# LEDboard.net
KiCad netlist of a schematic drawn in EAGLE
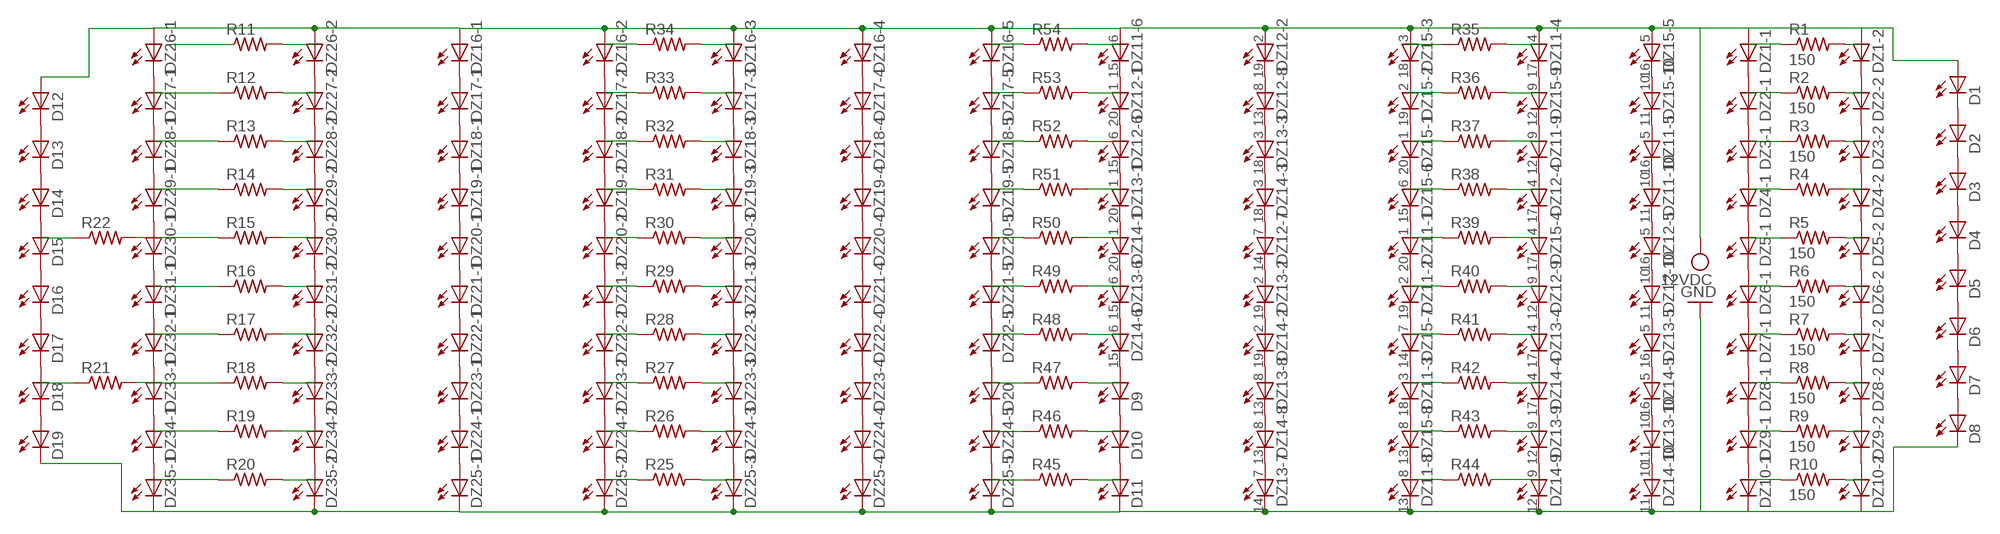
[diagram p0: schematic, sheet 1]

(export (version "E")
  (design (tool "Eeschema 10.0.6"))
  (components
    (comp (ref "D1")
      (value "U57X32")
      (footprint "eagle-import:U57X32")
      (libsource (lib "eagle-import") (part "U57X32"))
    )
    (comp (ref "D2")
      (value "U57X32")
      (footprint "eagle-import:U57X32")
      (libsource (lib "eagle-import") (part "U57X32"))
    )
    (comp (ref "D3")
      (value "U57X32")
      (footprint "eagle-import:U57X32")
      (libsource (lib "eagle-import") (part "U57X32"))
    )
    (comp (ref "D4")
      (value "U57X32")
      (footprint "eagle-import:U57X32")
      (libsource (lib "eagle-import") (part "U57X32"))
    )
    (comp (ref "D5")
      (value "U57X32")
      (footprint "eagle-import:U57X32")
      (libsource (lib "eagle-import") (part "U57X32"))
    )
    (comp (ref "D6")
      (value "U57X32")
      (footprint "eagle-import:U57X32")
      (libsource (lib "eagle-import") (part "U57X32"))
    )
    (comp (ref "D7")
      (value "U57X32")
      (footprint "eagle-import:U57X32")
      (libsource (lib "eagle-import") (part "U57X32"))
    )
    (comp (ref "D8")
      (value "U57X32")
      (footprint "eagle-import:U57X32")
      (libsource (lib "eagle-import") (part "U57X32"))
    )
    (comp (ref "D9")
      (value "U57X32")
      (footprint "eagle-import:U57X32")
      (libsource (lib "eagle-import") (part "U57X32"))
    )
    (comp (ref "D10")
      (value "U57X32")
      (footprint "eagle-import:U57X32")
      (libsource (lib "eagle-import") (part "U57X32"))
    )
    (comp (ref "D11")
      (value "U57X32")
      (footprint "eagle-import:U57X32")
      (libsource (lib "eagle-import") (part "U57X32"))
    )
    (comp (ref "D12")
      (value "U57X32")
      (footprint "eagle-import:U57X32")
      (libsource (lib "eagle-import") (part "U57X32"))
    )
    (comp (ref "D13")
      (value "U57X32")
      (footprint "eagle-import:U57X32")
      (libsource (lib "eagle-import") (part "U57X32"))
    )
    (comp (ref "D14")
      (value "U57X32")
      (footprint "eagle-import:U57X32")
      (libsource (lib "eagle-import") (part "U57X32"))
    )
    (comp (ref "D15")
      (value "U57X32")
      (footprint "eagle-import:U57X32")
      (libsource (lib "eagle-import") (part "U57X32"))
    )
    (comp (ref "D16")
      (value "U57X32")
      (footprint "eagle-import:U57X32")
      (libsource (lib "eagle-import") (part "U57X32"))
    )
    (comp (ref "D17")
      (value "U57X32")
      (footprint "eagle-import:U57X32")
      (libsource (lib "eagle-import") (part "U57X32"))
    )
    (comp (ref "D18")
      (value "U57X32")
      (footprint "eagle-import:U57X32")
      (libsource (lib "eagle-import") (part "U57X32"))
    )
    (comp (ref "D19")
      (value "U57X32")
      (footprint "eagle-import:U57X32")
      (libsource (lib "eagle-import") (part "U57X32"))
    )
    (comp (ref "D20")
      (value "U57X32")
      (footprint "eagle-import:U57X32")
      (libsource (lib "eagle-import") (part "U57X32"))
    )
    (comp (ref "DZ1")
      (value "LZR182")
      (footprint "eagle-import:LZR182")
      (libsource (lib "eagle-import") (part "LZR182"))
    )
    (comp (ref "DZ2")
      (value "LZR182")
      (footprint "eagle-import:LZR182")
      (libsource (lib "eagle-import") (part "LZR182"))
    )
    (comp (ref "DZ3")
      (value "LZR182")
      (footprint "eagle-import:LZR182")
      (libsource (lib "eagle-import") (part "LZR182"))
    )
    (comp (ref "DZ4")
      (value "LZR182")
      (footprint "eagle-import:LZR182")
      (libsource (lib "eagle-import") (part "LZR182"))
    )
    (comp (ref "DZ5")
      (value "LZR182")
      (footprint "eagle-import:LZR182")
      (libsource (lib "eagle-import") (part "LZR182"))
    )
    (comp (ref "DZ6")
      (value "LZR182")
      (footprint "eagle-import:LZR182")
      (libsource (lib "eagle-import") (part "LZR182"))
    )
    (comp (ref "DZ7")
      (value "LZR182")
      (footprint "eagle-import:LZR182")
      (libsource (lib "eagle-import") (part "LZR182"))
    )
    (comp (ref "DZ8")
      (value "LZR182")
      (footprint "eagle-import:LZR182")
      (libsource (lib "eagle-import") (part "LZR182"))
    )
    (comp (ref "DZ9")
      (value "LZR182")
      (footprint "eagle-import:LZR182")
      (libsource (lib "eagle-import") (part "LZR182"))
    )
    (comp (ref "DZ10")
      (value "LZR182")
      (footprint "eagle-import:LZR182")
      (libsource (lib "eagle-import") (part "LZR182"))
    )
    (comp (ref "DZ11")
      (value "LB10")
      (footprint "eagle-import:LB10")
      (libsource (lib "eagle-import") (part "LB10"))
    )
    (comp (ref "DZ12")
      (value "LB10")
      (footprint "eagle-import:LB10")
      (libsource (lib "eagle-import") (part "LB10"))
    )
    (comp (ref "DZ13")
      (value "LB10")
      (footprint "eagle-import:LB10")
      (libsource (lib "eagle-import") (part "LB10"))
    )
    (comp (ref "DZ14")
      (value "LB10")
      (footprint "eagle-import:LB10")
      (libsource (lib "eagle-import") (part "LB10"))
    )
    (comp (ref "DZ15")
      (value "LB10")
      (footprint "eagle-import:LB10")
      (libsource (lib "eagle-import") (part "LB10"))
    )
    (comp (ref "DZ16")
      (value "LZR185")
      (footprint "eagle-import:LZR185")
      (libsource (lib "eagle-import") (part "LZR185"))
    )
    (comp (ref "DZ17")
      (value "LZR185")
      (footprint "eagle-import:LZR185")
      (libsource (lib "eagle-import") (part "LZR185"))
    )
    (comp (ref "DZ18")
      (value "LZR185")
      (footprint "eagle-import:LZR185")
      (libsource (lib "eagle-import") (part "LZR185"))
    )
    (comp (ref "DZ19")
      (value "LZR185")
      (footprint "eagle-import:LZR185")
      (libsource (lib "eagle-import") (part "LZR185"))
    )
    (comp (ref "DZ20")
      (value "LZR185")
      (footprint "eagle-import:LZR185")
      (libsource (lib "eagle-import") (part "LZR185"))
    )
    (comp (ref "DZ21")
      (value "LZR185")
      (footprint "eagle-import:LZR185")
      (libsource (lib "eagle-import") (part "LZR185"))
    )
    (comp (ref "DZ22")
      (value "LZR185")
      (footprint "eagle-import:LZR185")
      (libsource (lib "eagle-import") (part "LZR185"))
    )
    (comp (ref "DZ23")
      (value "LZR185")
      (footprint "eagle-import:LZR185")
      (libsource (lib "eagle-import") (part "LZR185"))
    )
    (comp (ref "DZ24")
      (value "LZR185")
      (footprint "eagle-import:LZR185")
      (libsource (lib "eagle-import") (part "LZR185"))
    )
    (comp (ref "DZ25")
      (value "LZR185")
      (footprint "eagle-import:LZR185")
      (libsource (lib "eagle-import") (part "LZR185"))
    )
    (comp (ref "DZ26")
      (value "LZR182")
      (footprint "eagle-import:LZR182")
      (libsource (lib "eagle-import") (part "LZR182"))
    )
    (comp (ref "DZ27")
      (value "LZR182")
      (footprint "eagle-import:LZR182")
      (libsource (lib "eagle-import") (part "LZR182"))
    )
    (comp (ref "DZ28")
      (value "LZR182")
      (footprint "eagle-import:LZR182")
      (libsource (lib "eagle-import") (part "LZR182"))
    )
    (comp (ref "DZ29")
      (value "LZR182")
      (footprint "eagle-import:LZR182")
      (libsource (lib "eagle-import") (part "LZR182"))
    )
    (comp (ref "DZ30")
      (value "LZR182")
      (footprint "eagle-import:LZR182")
      (libsource (lib "eagle-import") (part "LZR182"))
    )
    (comp (ref "DZ31")
      (value "LZR182")
      (footprint "eagle-import:LZR182")
      (libsource (lib "eagle-import") (part "LZR182"))
    )
    (comp (ref "DZ32")
      (value "LZR182")
      (footprint "eagle-import:LZR182")
      (libsource (lib "eagle-import") (part "LZR182"))
    )
    (comp (ref "DZ33")
      (value "LZR182")
      (footprint "eagle-import:LZR182")
      (libsource (lib "eagle-import") (part "LZR182"))
    )
    (comp (ref "DZ34")
      (value "LZR182")
      (footprint "eagle-import:LZR182")
      (libsource (lib "eagle-import") (part "LZR182"))
    )
    (comp (ref "DZ35")
      (value "LZR182")
      (footprint "eagle-import:LZR182")
      (libsource (lib "eagle-import") (part "LZR182"))
    )
    (comp (ref "R1")
      (value "150")
      (footprint "eagle-import:0204V")
      (libsource (lib "eagle-import") (part "R-US_0204/2V"))
    )
    (comp (ref "R2")
      (value "150")
      (footprint "eagle-import:0204V")
      (libsource (lib "eagle-import") (part "R-US_0204/2V"))
    )
    (comp (ref "R3")
      (value "150")
      (footprint "eagle-import:0204V")
      (libsource (lib "eagle-import") (part "R-US_0204/2V"))
    )
    (comp (ref "R4")
      (value "R-US_0204/2V")
      (footprint "eagle-import:0204V")
      (libsource (lib "eagle-import") (part "R-US_0204/2V"))
    )
    (comp (ref "R5")
      (value "150")
      (footprint "eagle-import:0204V")
      (libsource (lib "eagle-import") (part "R-US_0204/2V"))
    )
    (comp (ref "R6")
      (value "150")
      (footprint "eagle-import:0204V")
      (libsource (lib "eagle-import") (part "R-US_0204/2V"))
    )
    (comp (ref "R7")
      (value "150")
      (footprint "eagle-import:0204V")
      (libsource (lib "eagle-import") (part "R-US_0204/2V"))
    )
    (comp (ref "R8")
      (value "150")
      (footprint "eagle-import:0204V")
      (libsource (lib "eagle-import") (part "R-US_0204/2V"))
    )
    (comp (ref "R9")
      (value "150")
      (footprint "eagle-import:0204V")
      (libsource (lib "eagle-import") (part "R-US_0204/2V"))
    )
    (comp (ref "R10")
      (value "150")
      (footprint "eagle-import:0204V")
      (libsource (lib "eagle-import") (part "R-US_0204/2V"))
    )
    (comp (ref "R11")
      (value "R-US_0204/2V")
      (footprint "eagle-import:0204V")
      (libsource (lib "eagle-import") (part "R-US_0204/2V"))
    )
    (comp (ref "R12")
      (value "R-US_0204/2V")
      (footprint "eagle-import:0204V")
      (libsource (lib "eagle-import") (part "R-US_0204/2V"))
    )
    (comp (ref "R13")
      (value "R-US_0204/2V")
      (footprint "eagle-import:0204V")
      (libsource (lib "eagle-import") (part "R-US_0204/2V"))
    )
    (comp (ref "R14")
      (value "R-US_0204/2V")
      (footprint "eagle-import:0204V")
      (libsource (lib "eagle-import") (part "R-US_0204/2V"))
    )
    (comp (ref "R15")
      (value "R-US_0204/2V")
      (footprint "eagle-import:0204V")
      (libsource (lib "eagle-import") (part "R-US_0204/2V"))
    )
    (comp (ref "R16")
      (value "R-US_0204/2V")
      (footprint "eagle-import:0204V")
      (libsource (lib "eagle-import") (part "R-US_0204/2V"))
    )
    (comp (ref "R17")
      (value "R-US_0204/2V")
      (footprint "eagle-import:0204V")
      (libsource (lib "eagle-import") (part "R-US_0204/2V"))
    )
    (comp (ref "R18")
      (value "R-US_0204/2V")
      (footprint "eagle-import:0204V")
      (libsource (lib "eagle-import") (part "R-US_0204/2V"))
    )
    (comp (ref "R19")
      (value "R-US_0204/2V")
      (footprint "eagle-import:0204V")
      (libsource (lib "eagle-import") (part "R-US_0204/2V"))
    )
    (comp (ref "R20")
      (value "R-US_0204/2V")
      (footprint "eagle-import:0204V")
      (libsource (lib "eagle-import") (part "R-US_0204/2V"))
    )
    (comp (ref "R21")
      (value "R-US_0204/2V")
      (footprint "eagle-import:0204V")
      (libsource (lib "eagle-import") (part "R-US_0204/2V"))
    )
    (comp (ref "R22")
      (value "R-US_0204/2V")
      (footprint "eagle-import:0204V")
      (libsource (lib "eagle-import") (part "R-US_0204/2V"))
    )
    (comp (ref "R25")
      (value "R-US_0204/2V")
      (footprint "eagle-import:0204V")
      (libsource (lib "eagle-import") (part "R-US_0204/2V"))
    )
    (comp (ref "R26")
      (value "R-US_0204/2V")
      (footprint "eagle-import:0204V")
      (libsource (lib "eagle-import") (part "R-US_0204/2V"))
    )
    (comp (ref "R27")
      (value "R-US_0204/2V")
      (footprint "eagle-import:0204V")
      (libsource (lib "eagle-import") (part "R-US_0204/2V"))
    )
    (comp (ref "R28")
      (value "R-US_0204/2V")
      (footprint "eagle-import:0204V")
      (libsource (lib "eagle-import") (part "R-US_0204/2V"))
    )
    (comp (ref "R29")
      (value "R-US_0204/2V")
      (footprint "eagle-import:0204V")
      (libsource (lib "eagle-import") (part "R-US_0204/2V"))
    )
    (comp (ref "R30")
      (value "R-US_0204/2V")
      (footprint "eagle-import:0204V")
      (libsource (lib "eagle-import") (part "R-US_0204/2V"))
    )
    (comp (ref "R31")
      (value "R-US_0204/2V")
      (footprint "eagle-import:0204V")
      (libsource (lib "eagle-import") (part "R-US_0204/2V"))
    )
    (comp (ref "R32")
      (value "R-US_0204/2V")
      (footprint "eagle-import:0204V")
      (libsource (lib "eagle-import") (part "R-US_0204/2V"))
    )
    (comp (ref "R33")
      (value "R-US_0204/2V")
      (footprint "eagle-import:0204V")
      (libsource (lib "eagle-import") (part "R-US_0204/2V"))
    )
    (comp (ref "R34")
      (value "R-US_0204/2V")
      (footprint "eagle-import:0204V")
      (libsource (lib "eagle-import") (part "R-US_0204/2V"))
    )
    (comp (ref "R35")
      (value "R-US_0204/2V")
      (footprint "eagle-import:0204V")
      (libsource (lib "eagle-import") (part "R-US_0204/2V"))
    )
    (comp (ref "R36")
      (value "R-US_0204/2V")
      (footprint "eagle-import:0204V")
      (libsource (lib "eagle-import") (part "R-US_0204/2V"))
    )
    (comp (ref "R37")
      (value "R-US_0204/2V")
      (footprint "eagle-import:0204V")
      (libsource (lib "eagle-import") (part "R-US_0204/2V"))
    )
    (comp (ref "R38")
      (value "R-US_0204/2V")
      (footprint "eagle-import:0204V")
      (libsource (lib "eagle-import") (part "R-US_0204/2V"))
    )
    (comp (ref "R39")
      (value "R-US_0204/2V")
      (footprint "eagle-import:0204V")
      (libsource (lib "eagle-import") (part "R-US_0204/2V"))
    )
    (comp (ref "R40")
      (value "R-US_0204/2V")
      (footprint "eagle-import:0204V")
      (libsource (lib "eagle-import") (part "R-US_0204/2V"))
    )
    (comp (ref "R41")
      (value "R-US_0204/2V")
      (footprint "eagle-import:0204V")
      (libsource (lib "eagle-import") (part "R-US_0204/2V"))
    )
    (comp (ref "R42")
      (value "R-US_0204/2V")
      (footprint "eagle-import:0204V")
      (libsource (lib "eagle-import") (part "R-US_0204/2V"))
    )
    (comp (ref "R43")
      (value "R-US_0204/2V")
      (footprint "eagle-import:0204V")
      (libsource (lib "eagle-import") (part "R-US_0204/2V"))
    )
    (comp (ref "R44")
      (value "R-US_0204/2V")
      (footprint "eagle-import:0204V")
      (libsource (lib "eagle-import") (part "R-US_0204/2V"))
    )
    (comp (ref "R45")
      (value "R-US_0204/2V")
      (footprint "eagle-import:0204V")
      (libsource (lib "eagle-import") (part "R-US_0204/2V"))
    )
    (comp (ref "R46")
      (value "R-US_0204/2V")
      (footprint "eagle-import:0204V")
      (libsource (lib "eagle-import") (part "R-US_0204/2V"))
    )
    (comp (ref "R47")
      (value "R-US_0204/2V")
      (footprint "eagle-import:0204V")
      (libsource (lib "eagle-import") (part "R-US_0204/2V"))
    )
    (comp (ref "R48")
      (value "R-US_0204/2V")
      (footprint "eagle-import:0204V")
      (libsource (lib "eagle-import") (part "R-US_0204/2V"))
    )
    (comp (ref "R49")
      (value "R-US_0204/2V")
      (footprint "eagle-import:0204V")
      (libsource (lib "eagle-import") (part "R-US_0204/2V"))
    )
    (comp (ref "R50")
      (value "R-US_0204/2V")
      (footprint "eagle-import:0204V")
      (libsource (lib "eagle-import") (part "R-US_0204/2V"))
    )
    (comp (ref "R51")
      (value "R-US_0204/2V")
      (footprint "eagle-import:0204V")
      (libsource (lib "eagle-import") (part "R-US_0204/2V"))
    )
    (comp (ref "R52")
      (value "R-US_0204/2V")
      (footprint "eagle-import:0204V")
      (libsource (lib "eagle-import") (part "R-US_0204/2V"))
    )
    (comp (ref "R53")
      (value "R-US_0204/2V")
      (footprint "eagle-import:0204V")
      (libsource (lib "eagle-import") (part "R-US_0204/2V"))
    )
    (comp (ref "R54")
      (value "R-US_0204/2V")
      (footprint "eagle-import:0204V")
      (libsource (lib "eagle-import") (part "R-US_0204/2V"))
    )
  )
  (nets
    (net (code "1") (name "12VDC") (class "Default")
      (node (ref "D1") (pin "A") (pinfunction "A_A") (pintype "passive"))
      (node (ref "D12") (pin "A") (pinfunction "A_A") (pintype "passive"))
      (node (ref "DZ1") (pin "A1") (pinfunction "A_A1") (pintype "passive"))
      (node (ref "DZ1") (pin "A2") (pinfunction "A_A2") (pintype "passive"))
      (node (ref "DZ11") (pin "4") (pinfunction "A_4") (pintype "passive"))
      (node (ref "DZ11") (pin "6") (pinfunction "A_6") (pintype "passive"))
      (node (ref "DZ12") (pin "2") (pinfunction "A_2") (pintype "passive"))
      (node (ref "DZ15") (pin "3") (pinfunction "A_3") (pintype "passive"))
      (node (ref "DZ15") (pin "5") (pinfunction "A_5") (pintype "passive"))
      (node (ref "DZ16") (pin "A1") (pinfunction "A_A1") (pintype "passive"))
      (node (ref "DZ16") (pin "A2") (pinfunction "A_A2") (pintype "passive"))
      (node (ref "DZ16") (pin "A3") (pinfunction "A_A3") (pintype "passive"))
      (node (ref "DZ16") (pin "A4") (pinfunction "A_A4") (pintype "passive"))
      (node (ref "DZ16") (pin "A5") (pinfunction "A_A5") (pintype "passive"))
      (node (ref "DZ26") (pin "A1") (pinfunction "A_A1") (pintype "passive"))
      (node (ref "DZ26") (pin "A2") (pinfunction "A_A2") (pintype "passive"))
    )
    (net (code "2") (name "GND") (class "Default")
      (node (ref "D11") (pin "K") (pinfunction "C_K") (pintype "passive"))
      (node (ref "D19") (pin "K") (pinfunction "C_K") (pintype "passive"))
      (node (ref "D8") (pin "K") (pinfunction "C_K") (pintype "passive"))
      (node (ref "DZ10") (pin "K1") (pinfunction "C_K1") (pintype "passive"))
      (node (ref "DZ10") (pin "K2") (pinfunction "C_K2") (pintype "passive"))
      (node (ref "DZ11") (pin "13") (pinfunction "C_13") (pintype "passive"))
      (node (ref "DZ13") (pin "14") (pinfunction "C_14") (pintype "passive"))
      (node (ref "DZ14") (pin "11") (pinfunction "C_11") (pintype "passive"))
      (node (ref "DZ14") (pin "12") (pinfunction "C_12") (pintype "passive"))
      (node (ref "DZ25") (pin "K1") (pinfunction "C_K1") (pintype "passive"))
      (node (ref "DZ25") (pin "K2") (pinfunction "C_K2") (pintype "passive"))
      (node (ref "DZ25") (pin "K3") (pinfunction "C_K3") (pintype "passive"))
      (node (ref "DZ25") (pin "K4") (pinfunction "C_K4") (pintype "passive"))
      (node (ref "DZ25") (pin "K5") (pinfunction "C_K5") (pintype "passive"))
      (node (ref "DZ35") (pin "K1") (pinfunction "C_K1") (pintype "passive"))
      (node (ref "DZ35") (pin "K2") (pinfunction "C_K2") (pintype "passive"))
    )
    (net (code "3") (name "Net-(D1-C)") (class "Default")
      (node (ref "D1") (pin "K") (pinfunction "C_K") (pintype "passive"))
      (node (ref "D2") (pin "A") (pinfunction "A_A") (pintype "passive"))
    )
    (net (code "4") (name "Net-(D2-C)") (class "Default")
      (node (ref "D2") (pin "K") (pinfunction "C_K") (pintype "passive"))
      (node (ref "D3") (pin "A") (pinfunction "A_A") (pintype "passive"))
    )
    (net (code "5") (name "Net-(D3-C)") (class "Default")
      (node (ref "D3") (pin "K") (pinfunction "C_K") (pintype "passive"))
      (node (ref "D4") (pin "A") (pinfunction "A_A") (pintype "passive"))
    )
    (net (code "6") (name "Net-(D4-C)") (class "Default")
      (node (ref "D4") (pin "K") (pinfunction "C_K") (pintype "passive"))
      (node (ref "D5") (pin "A") (pinfunction "A_A") (pintype "passive"))
    )
    (net (code "7") (name "Net-(D5-C)") (class "Default")
      (node (ref "D5") (pin "K") (pinfunction "C_K") (pintype "passive"))
      (node (ref "D6") (pin "A") (pinfunction "A_A") (pintype "passive"))
    )
    (net (code "8") (name "Net-(D6-C)") (class "Default")
      (node (ref "D6") (pin "K") (pinfunction "C_K") (pintype "passive"))
      (node (ref "D7") (pin "A") (pinfunction "A_A") (pintype "passive"))
    )
    (net (code "9") (name "Net-(D7-C)") (class "Default")
      (node (ref "D7") (pin "K") (pinfunction "C_K") (pintype "passive"))
      (node (ref "D8") (pin "A") (pinfunction "A_A") (pintype "passive"))
    )
    (net (code "10") (name "Net-(D9-C)") (class "Default")
      (node (ref "D10") (pin "A") (pinfunction "A_A") (pintype "passive"))
      (node (ref "D9") (pin "K") (pinfunction "C_K") (pintype "passive"))
    )
    (net (code "11") (name "Net-(D10-C)") (class "Default")
      (node (ref "D10") (pin "K") (pinfunction "C_K") (pintype "passive"))
      (node (ref "D11") (pin "A") (pinfunction "A_A") (pintype "passive"))
    )
    (net (code "12") (name "Net-(D12-C)") (class "Default")
      (node (ref "D12") (pin "K") (pinfunction "C_K") (pintype "passive"))
      (node (ref "D13") (pin "A") (pinfunction "A_A") (pintype "passive"))
    )
    (net (code "13") (name "Net-(D13-C)") (class "Default")
      (node (ref "D13") (pin "K") (pinfunction "C_K") (pintype "passive"))
      (node (ref "D14") (pin "A") (pinfunction "A_A") (pintype "passive"))
    )
    (net (code "14") (name "Net-(D14-C)") (class "Default")
      (node (ref "D14") (pin "K") (pinfunction "C_K") (pintype "passive"))
      (node (ref "D15") (pin "A") (pinfunction "A_A") (pintype "passive"))
    )
    (net (code "15") (name "Net-(D15-C)") (class "Default")
      (node (ref "D15") (pin "K") (pinfunction "C_K") (pintype "passive"))
      (node (ref "D16") (pin "A") (pinfunction "A_A") (pintype "passive"))
    )
    (net (code "16") (name "Net-(D16-C)") (class "Default")
      (node (ref "D16") (pin "K") (pinfunction "C_K") (pintype "passive"))
      (node (ref "D17") (pin "A") (pinfunction "A_A") (pintype "passive"))
    )
    (net (code "17") (name "Net-(D17-C)") (class "Default")
      (node (ref "D17") (pin "K") (pinfunction "C_K") (pintype "passive"))
      (node (ref "D18") (pin "A") (pinfunction "A_A") (pintype "passive"))
    )
    (net (code "18") (name "Net-(D18-C)") (class "Default")
      (node (ref "D18") (pin "K") (pinfunction "C_K") (pintype "passive"))
      (node (ref "D19") (pin "A") (pinfunction "A_A") (pintype "passive"))
    )
    (net (code "19") (name "Net-(D20-C)") (class "Default")
      (node (ref "D20") (pin "K") (pinfunction "C_K") (pintype "passive"))
      (node (ref "DZ24") (pin "A5") (pinfunction "A_A5") (pintype "passive"))
    )
    (net (code "20") (name "Net-(DZ1A-C)") (class "Default")
      (node (ref "DZ1") (pin "K1") (pinfunction "C_K1") (pintype "passive"))
      (node (ref "DZ2") (pin "A1") (pinfunction "A_A1") (pintype "passive"))
    )
    (net (code "21") (name "Net-(DZ1B-C)") (class "Default")
      (node (ref "DZ1") (pin "K2") (pinfunction "C_K2") (pintype "passive"))
      (node (ref "DZ2") (pin "A2") (pinfunction "A_A2") (pintype "passive"))
    )
    (net (code "22") (name "Net-(DZ2A-C)") (class "Default")
      (node (ref "DZ2") (pin "K1") (pinfunction "C_K1") (pintype "passive"))
      (node (ref "DZ3") (pin "A1") (pinfunction "A_A1") (pintype "passive"))
    )
    (net (code "23") (name "Net-(DZ2B-C)") (class "Default")
      (node (ref "DZ2") (pin "K2") (pinfunction "C_K2") (pintype "passive"))
      (node (ref "DZ3") (pin "A2") (pinfunction "A_A2") (pintype "passive"))
    )
    (net (code "24") (name "Net-(DZ3A-C)") (class "Default")
      (node (ref "DZ3") (pin "K1") (pinfunction "C_K1") (pintype "passive"))
      (node (ref "DZ4") (pin "A1") (pinfunction "A_A1") (pintype "passive"))
    )
    (net (code "25") (name "Net-(DZ3B-C)") (class "Default")
      (node (ref "DZ3") (pin "K2") (pinfunction "C_K2") (pintype "passive"))
      (node (ref "DZ4") (pin "A2") (pinfunction "A_A2") (pintype "passive"))
    )
    (net (code "26") (name "Net-(DZ4A-C)") (class "Default")
      (node (ref "DZ4") (pin "K1") (pinfunction "C_K1") (pintype "passive"))
      (node (ref "DZ5") (pin "A1") (pinfunction "A_A1") (pintype "passive"))
    )
    (net (code "27") (name "Net-(DZ4B-C)") (class "Default")
      (node (ref "DZ4") (pin "K2") (pinfunction "C_K2") (pintype "passive"))
      (node (ref "DZ5") (pin "A2") (pinfunction "A_A2") (pintype "passive"))
    )
    (net (code "28") (name "Net-(DZ5A-C)") (class "Default")
      (node (ref "DZ5") (pin "K1") (pinfunction "C_K1") (pintype "passive"))
      (node (ref "DZ6") (pin "A1") (pinfunction "A_A1") (pintype "passive"))
    )
    (net (code "29") (name "Net-(DZ5B-C)") (class "Default")
      (node (ref "DZ5") (pin "K2") (pinfunction "C_K2") (pintype "passive"))
      (node (ref "DZ6") (pin "A2") (pinfunction "A_A2") (pintype "passive"))
    )
    (net (code "30") (name "Net-(DZ6A-C)") (class "Default")
      (node (ref "DZ6") (pin "K1") (pinfunction "C_K1") (pintype "passive"))
      (node (ref "DZ7") (pin "A1") (pinfunction "A_A1") (pintype "passive"))
    )
    (net (code "31") (name "Net-(DZ6B-C)") (class "Default")
      (node (ref "DZ6") (pin "K2") (pinfunction "C_K2") (pintype "passive"))
      (node (ref "DZ7") (pin "A2") (pinfunction "A_A2") (pintype "passive"))
    )
    (net (code "32") (name "Net-(DZ7A-C)") (class "Default")
      (node (ref "DZ7") (pin "K1") (pinfunction "C_K1") (pintype "passive"))
      (node (ref "DZ8") (pin "A1") (pinfunction "A_A1") (pintype "passive"))
    )
    (net (code "33") (name "Net-(DZ7B-C)") (class "Default")
      (node (ref "DZ7") (pin "K2") (pinfunction "C_K2") (pintype "passive"))
      (node (ref "DZ8") (pin "A2") (pinfunction "A_A2") (pintype "passive"))
    )
    (net (code "34") (name "Net-(DZ8A-C)") (class "Default")
      (node (ref "DZ8") (pin "K1") (pinfunction "C_K1") (pintype "passive"))
      (node (ref "DZ9") (pin "A1") (pinfunction "A_A1") (pintype "passive"))
    )
    (net (code "35") (name "Net-(DZ8B-C)") (class "Default")
      (node (ref "DZ8") (pin "K2") (pinfunction "C_K2") (pintype "passive"))
      (node (ref "DZ9") (pin "A2") (pinfunction "A_A2") (pintype "passive"))
    )
    (net (code "36") (name "Net-(DZ10A-A)") (class "Default")
      (node (ref "DZ10") (pin "A1") (pinfunction "A_A1") (pintype "passive"))
      (node (ref "DZ9") (pin "K1") (pinfunction "C_K1") (pintype "passive"))
    )
    (net (code "37") (name "Net-(DZ10B-A)") (class "Default")
      (node (ref "DZ10") (pin "A2") (pinfunction "A_A2") (pintype "passive"))
      (node (ref "DZ9") (pin "K2") (pinfunction "C_K2") (pintype "passive"))
    )
    (net (code "38") (name "Net-(DZ11A-A)") (class "Default")
      (node (ref "DZ11") (pin "1") (pinfunction "A_1") (pintype "passive"))
      (node (ref "DZ15") (pin "15") (pinfunction "C_15") (pintype "passive"))
    )
    (net (code "39") (name "Net-(DZ11A-C)") (class "Default")
      (node (ref "DZ11") (pin "2") (pinfunction "A_2") (pintype "passive"))
      (node (ref "DZ11") (pin "20") (pinfunction "C_20") (pintype "passive"))
    )
    (net (code "40") (name "Net-(DZ11B-A)") (class "Default")
      (node (ref "DZ11") (pin "10") (pinfunction "A_10") (pintype "passive"))
      (node (ref "DZ11") (pin "16") (pinfunction "C_16") (pintype "passive"))
    )
    (net (code "41") (name "Net-(DZ11B-C)") (class "Default")
      (node (ref "DZ11") (pin "11") (pinfunction "C_11") (pintype "passive"))
      (node (ref "DZ12") (pin "5") (pinfunction "A_5") (pintype "passive"))
    )
    (net (code "42") (name "Net-(DZ11C-C)") (class "Default")
      (node (ref "DZ11") (pin "19") (pinfunction "C_19") (pintype "passive"))
      (node (ref "DZ15") (pin "7") (pinfunction "A_7") (pintype "passive"))
    )
    (net (code "43") (name "Net-(DZ11D-A)") (class "Default")
      (node (ref "DZ11") (pin "3") (pinfunction "A_3") (pintype "passive"))
      (node (ref "DZ15") (pin "14") (pinfunction "C_14") (pintype "passive"))
    )
    (net (code "44") (name "Net-(DZ11D-C)") (class "Default")
      (node (ref "DZ11") (pin "18") (pinfunction "C_18") (pintype "passive"))
      (node (ref "DZ15") (pin "8") (pinfunction "A_8") (pintype "passive"))
    )
    (net (code "45") (name "Net-(DZ11E-C)") (class "Default")
      (node (ref "DZ11") (pin "17") (pinfunction "C_17") (pintype "passive"))
      (node (ref "DZ15") (pin "9") (pinfunction "A_9") (pintype "passive"))
    )
    (net (code "46") (name "Net-(DZ11F-A)") (class "Default")
      (node (ref "DZ11") (pin "5") (pinfunction "A_5") (pintype "passive"))
      (node (ref "DZ15") (pin "11") (pinfunction "C_11") (pintype "passive"))
    )
    (net (code "47") (name "Net-(DZ11G-C)") (class "Default")
      (node (ref "DZ11") (pin "15") (pinfunction "C_15") (pintype "passive"))
      (node (ref "DZ12") (pin "1") (pinfunction "A_1") (pintype "passive"))
    )
    (net (code "48") (name "Net-(DZ11I-A)") (class "Default")
      (node (ref "DZ11") (pin "8") (pinfunction "A_8") (pintype "passive"))
      (node (ref "DZ15") (pin "13") (pinfunction "C_13") (pintype "passive"))
    )
    (net (code "49") (name "Net-(DZ11J-A)") (class "Default")
      (node (ref "DZ11") (pin "9") (pinfunction "A_9") (pintype "passive"))
      (node (ref "DZ15") (pin "12") (pinfunction "C_12") (pintype "passive"))
    )
    (net (code "50") (name "Net-(DZ11J-C)") (class "Default")
      (node (ref "DZ11") (pin "12") (pinfunction "C_12") (pintype "passive"))
      (node (ref "DZ12") (pin "4") (pinfunction "A_4") (pintype "passive"))
    )
    (net (code "51") (name "Net-(DZ12A-C)") (class "Default")
      (node (ref "DZ12") (pin "20") (pinfunction "C_20") (pintype "passive"))
      (node (ref "DZ12") (pin "6") (pinfunction "A_6") (pintype "passive"))
    )
    (net (code "52") (name "Net-(DZ12B-A)") (class "Default")
      (node (ref "DZ12") (pin "10") (pinfunction "A_10") (pintype "passive"))
      (node (ref "DZ12") (pin "16") (pinfunction "C_16") (pintype "passive"))
    )
    (net (code "53") (name "Net-(DZ12B-C)") (class "Default")
      (node (ref "DZ12") (pin "11") (pinfunction "C_11") (pintype "passive"))
      (node (ref "DZ13") (pin "5") (pinfunction "A_5") (pintype "passive"))
    )
    (net (code "54") (name "Net-(DZ12C-C)") (class "Default")
      (node (ref "DZ12") (pin "19") (pinfunction "C_19") (pintype "passive"))
      (node (ref "DZ12") (pin "8") (pinfunction "A_8") (pintype "passive"))
    )
    (net (code "55") (name "Net-(DZ12E-C)") (class "Default")
      (node (ref "DZ12") (pin "17") (pinfunction "C_17") (pintype "passive"))
      (node (ref "DZ15") (pin "4") (pinfunction "A_4") (pintype "passive"))
    )
    (net (code "56") (name "Net-(DZ12G-C)") (class "Default")
      (node (ref "DZ12") (pin "15") (pinfunction "C_15") (pintype "passive"))
      (node (ref "DZ13") (pin "1") (pinfunction "A_1") (pintype "passive"))
    )
    (net (code "57") (name "Net-(DZ12H-A)") (class "Default")
      (node (ref "DZ12") (pin "7") (pinfunction "A_7") (pintype "passive"))
      (node (ref "DZ14") (pin "18") (pinfunction "C_18") (pintype "passive"))
    )
    (net (code "58") (name "Net-(DZ12H-C)") (class "Default")
      (node (ref "DZ12") (pin "14") (pinfunction "C_14") (pintype "passive"))
      (node (ref "DZ13") (pin "2") (pinfunction "A_2") (pintype "passive"))
    )
    (net (code "59") (name "Net-(DZ12I-C)") (class "Default")
      (node (ref "DZ12") (pin "13") (pinfunction "C_13") (pintype "passive"))
      (node (ref "DZ13") (pin "3") (pinfunction "A_3") (pintype "passive"))
    )
    (net (code "60") (name "Net-(DZ12J-A)") (class "Default")
      (node (ref "DZ12") (pin "9") (pinfunction "A_9") (pintype "passive"))
      (node (ref "DZ15") (pin "17") (pinfunction "C_17") (pintype "passive"))
    )
    (net (code "61") (name "Net-(DZ12J-C)") (class "Default")
      (node (ref "DZ12") (pin "12") (pinfunction "C_12") (pintype "passive"))
      (node (ref "DZ13") (pin "4") (pinfunction "A_4") (pintype "passive"))
    )
    (net (code "62") (name "Net-(DZ13A-C)") (class "Default")
      (node (ref "DZ13") (pin "20") (pinfunction "C_20") (pintype "passive"))
      (node (ref "DZ14") (pin "1") (pinfunction "A_1") (pintype "passive"))
    )
    (net (code "63") (name "Net-(DZ13B-A)") (class "Default")
      (node (ref "DZ13") (pin "10") (pinfunction "A_10") (pintype "passive"))
      (node (ref "DZ14") (pin "16") (pinfunction "C_16") (pintype "passive"))
    )
    (net (code "64") (name "Net-(DZ13B-C)") (class "Default")
      (node (ref "DZ13") (pin "11") (pinfunction "C_11") (pintype "passive"))
      (node (ref "DZ14") (pin "10") (pinfunction "A_10") (pintype "passive"))
    )
    (net (code "65") (name "Net-(DZ13C-C)") (class "Default")
      (node (ref "DZ13") (pin "19") (pinfunction "C_19") (pintype "passive"))
      (node (ref "DZ14") (pin "2") (pinfunction "A_2") (pintype "passive"))
    )
    (net (code "66") (name "Net-(DZ13D-C)") (class "Default")
      (node (ref "DZ13") (pin "18") (pinfunction "C_18") (pintype "passive"))
      (node (ref "DZ14") (pin "3") (pinfunction "A_3") (pintype "passive"))
    )
    (net (code "67") (name "Net-(DZ13E-C)") (class "Default")
      (node (ref "DZ13") (pin "17") (pinfunction "C_17") (pintype "passive"))
      (node (ref "DZ14") (pin "4") (pinfunction "A_4") (pintype "passive"))
    )
    (net (code "68") (name "Net-(DZ13F-C)") (class "Default")
      (node (ref "DZ13") (pin "16") (pinfunction "C_16") (pintype "passive"))
      (node (ref "DZ14") (pin "5") (pinfunction "A_5") (pintype "passive"))
    )
    (net (code "69") (name "Net-(DZ13G-A)") (class "Default")
      (node (ref "DZ13") (pin "6") (pinfunction "A_6") (pintype "passive"))
      (node (ref "DZ14") (pin "20") (pinfunction "C_20") (pintype "passive"))
    )
    (net (code "70") (name "Net-(DZ13G-C)") (class "Default")
      (node (ref "DZ13") (pin "15") (pinfunction "C_15") (pintype "passive"))
      (node (ref "DZ14") (pin "6") (pinfunction "A_6") (pintype "passive"))
    )
    (net (code "71") (name "Net-(DZ13H-A)") (class "Default")
      (node (ref "DZ13") (pin "7") (pinfunction "A_7") (pintype "passive"))
      (node (ref "DZ14") (pin "13") (pinfunction "C_13") (pintype "passive"))
    )
    (net (code "72") (name "Net-(DZ13I-A)") (class "Default")
      (node (ref "DZ13") (pin "8") (pinfunction "A_8") (pintype "passive"))
      (node (ref "DZ14") (pin "19") (pinfunction "C_19") (pintype "passive"))
    )
    (net (code "73") (name "Net-(DZ13I-C)") (class "Default")
      (node (ref "DZ13") (pin "13") (pinfunction "C_13") (pintype "passive"))
      (node (ref "DZ14") (pin "8") (pinfunction "A_8") (pintype "passive"))
    )
    (net (code "74") (name "Net-(DZ13J-A)") (class "Default")
      (node (ref "DZ13") (pin "9") (pinfunction "A_9") (pintype "passive"))
      (node (ref "DZ14") (pin "17") (pinfunction "C_17") (pintype "passive"))
    )
    (net (code "75") (name "Net-(DZ13J-C)") (class "Default")
      (node (ref "DZ13") (pin "12") (pinfunction "C_12") (pintype "passive"))
      (node (ref "DZ14") (pin "9") (pinfunction "A_9") (pintype "passive"))
    )
    (net (code "76") (name "Net-(DZ14G-C)") (class "Default")
      (node (ref "D9") (pin "A") (pinfunction "A_A") (pintype "passive"))
      (node (ref "DZ14") (pin "15") (pinfunction "C_15") (pintype "passive"))
    )
    (net (code "77") (name "Net-(DZ15A-A)") (class "Default")
      (node (ref "DZ15") (pin "1") (pinfunction "A_1") (pintype "passive"))
      (node (ref "DZ15") (pin "19") (pinfunction "C_19") (pintype "passive"))
    )
    (net (code "78") (name "Net-(DZ15A-C)") (class "Default")
      (node (ref "DZ15") (pin "20") (pinfunction "C_20") (pintype "passive"))
      (node (ref "DZ15") (pin "6") (pinfunction "A_6") (pintype "passive"))
    )
    (net (code "79") (name "Net-(DZ15B-A)") (class "Default")
      (node (ref "DZ15") (pin "10") (pinfunction "A_10") (pintype "passive"))
      (node (ref "DZ15") (pin "16") (pinfunction "C_16") (pintype "passive"))
    )
    (net (code "80") (name "Net-(DZ15C-A)") (class "Default")
      (node (ref "DZ15") (pin "18") (pinfunction "C_18") (pintype "passive"))
      (node (ref "DZ15") (pin "2") (pinfunction "A_2") (pintype "passive"))
    )
    (net (code "81") (name "Net-(DZ16A-C)") (class "Default")
      (node (ref "DZ16") (pin "K1") (pinfunction "C_K1") (pintype "passive"))
      (node (ref "DZ17") (pin "A1") (pinfunction "A_A1") (pintype "passive"))
    )
    (net (code "82") (name "Net-(DZ16B-C)") (class "Default")
      (node (ref "DZ16") (pin "K2") (pinfunction "C_K2") (pintype "passive"))
      (node (ref "DZ17") (pin "A2") (pinfunction "A_A2") (pintype "passive"))
    )
    (net (code "83") (name "Net-(DZ16C-C)") (class "Default")
      (node (ref "DZ16") (pin "K3") (pinfunction "C_K3") (pintype "passive"))
      (node (ref "DZ17") (pin "A3") (pinfunction "A_A3") (pintype "passive"))
    )
    (net (code "84") (name "Net-(DZ16D-C)") (class "Default")
      (node (ref "DZ16") (pin "K4") (pinfunction "C_K4") (pintype "passive"))
      (node (ref "DZ17") (pin "A4") (pinfunction "A_A4") (pintype "passive"))
    )
    (net (code "85") (name "Net-(DZ16E-C)") (class "Default")
      (node (ref "DZ16") (pin "K5") (pinfunction "C_K5") (pintype "passive"))
      (node (ref "DZ17") (pin "A5") (pinfunction "A_A5") (pintype "passive"))
    )
    (net (code "86") (name "Net-(DZ17A-C)") (class "Default")
      (node (ref "DZ17") (pin "K1") (pinfunction "C_K1") (pintype "passive"))
      (node (ref "DZ18") (pin "A1") (pinfunction "A_A1") (pintype "passive"))
    )
    (net (code "87") (name "Net-(DZ17B-C)") (class "Default")
      (node (ref "DZ17") (pin "K2") (pinfunction "C_K2") (pintype "passive"))
      (node (ref "DZ18") (pin "A2") (pinfunction "A_A2") (pintype "passive"))
    )
    (net (code "88") (name "Net-(DZ17C-C)") (class "Default")
      (node (ref "DZ17") (pin "K3") (pinfunction "C_K3") (pintype "passive"))
      (node (ref "DZ18") (pin "A3") (pinfunction "A_A3") (pintype "passive"))
    )
    (net (code "89") (name "Net-(DZ17D-C)") (class "Default")
      (node (ref "DZ17") (pin "K4") (pinfunction "C_K4") (pintype "passive"))
      (node (ref "DZ18") (pin "A4") (pinfunction "A_A4") (pintype "passive"))
    )
    (net (code "90") (name "Net-(DZ17E-C)") (class "Default")
      (node (ref "DZ17") (pin "K5") (pinfunction "C_K5") (pintype "passive"))
      (node (ref "DZ18") (pin "A5") (pinfunction "A_A5") (pintype "passive"))
    )
    (net (code "91") (name "Net-(DZ18A-C)") (class "Default")
      (node (ref "DZ18") (pin "K1") (pinfunction "C_K1") (pintype "passive"))
      (node (ref "DZ19") (pin "A1") (pinfunction "A_A1") (pintype "passive"))
    )
    (net (code "92") (name "Net-(DZ18B-C)") (class "Default")
      (node (ref "DZ18") (pin "K2") (pinfunction "C_K2") (pintype "passive"))
      (node (ref "DZ19") (pin "A2") (pinfunction "A_A2") (pintype "passive"))
    )
    (net (code "93") (name "Net-(DZ18C-C)") (class "Default")
      (node (ref "DZ18") (pin "K3") (pinfunction "C_K3") (pintype "passive"))
      (node (ref "DZ19") (pin "A3") (pinfunction "A_A3") (pintype "passive"))
    )
    (net (code "94") (name "Net-(DZ18D-C)") (class "Default")
      (node (ref "DZ18") (pin "K4") (pinfunction "C_K4") (pintype "passive"))
      (node (ref "DZ19") (pin "A4") (pinfunction "A_A4") (pintype "passive"))
    )
    (net (code "95") (name "Net-(DZ18E-C)") (class "Default")
      (node (ref "DZ18") (pin "K5") (pinfunction "C_K5") (pintype "passive"))
      (node (ref "DZ19") (pin "A5") (pinfunction "A_A5") (pintype "passive"))
    )
    (net (code "96") (name "Net-(DZ19A-C)") (class "Default")
      (node (ref "DZ19") (pin "K1") (pinfunction "C_K1") (pintype "passive"))
      (node (ref "DZ20") (pin "A1") (pinfunction "A_A1") (pintype "passive"))
    )
    (net (code "97") (name "Net-(DZ19B-C)") (class "Default")
      (node (ref "DZ19") (pin "K2") (pinfunction "C_K2") (pintype "passive"))
      (node (ref "DZ20") (pin "A2") (pinfunction "A_A2") (pintype "passive"))
    )
    (net (code "98") (name "Net-(DZ19C-C)") (class "Default")
      (node (ref "DZ19") (pin "K3") (pinfunction "C_K3") (pintype "passive"))
      (node (ref "DZ20") (pin "A3") (pinfunction "A_A3") (pintype "passive"))
    )
    (net (code "99") (name "Net-(DZ19D-C)") (class "Default")
      (node (ref "DZ19") (pin "K4") (pinfunction "C_K4") (pintype "passive"))
      (node (ref "DZ20") (pin "A4") (pinfunction "A_A4") (pintype "passive"))
    )
    (net (code "100") (name "Net-(DZ19E-C)") (class "Default")
      (node (ref "DZ19") (pin "K5") (pinfunction "C_K5") (pintype "passive"))
      (node (ref "DZ20") (pin "A5") (pinfunction "A_A5") (pintype "passive"))
    )
    (net (code "101") (name "Net-(DZ20A-C)") (class "Default")
      (node (ref "DZ20") (pin "K1") (pinfunction "C_K1") (pintype "passive"))
      (node (ref "DZ21") (pin "A1") (pinfunction "A_A1") (pintype "passive"))
    )
    (net (code "102") (name "Net-(DZ20B-C)") (class "Default")
      (node (ref "DZ20") (pin "K2") (pinfunction "C_K2") (pintype "passive"))
      (node (ref "DZ21") (pin "A2") (pinfunction "A_A2") (pintype "passive"))
    )
    (net (code "103") (name "Net-(DZ20C-C)") (class "Default")
      (node (ref "DZ20") (pin "K3") (pinfunction "C_K3") (pintype "passive"))
      (node (ref "DZ21") (pin "A3") (pinfunction "A_A3") (pintype "passive"))
    )
    (net (code "104") (name "Net-(DZ20D-C)") (class "Default")
      (node (ref "DZ20") (pin "K4") (pinfunction "C_K4") (pintype "passive"))
      (node (ref "DZ21") (pin "A4") (pinfunction "A_A4") (pintype "passive"))
    )
    (net (code "105") (name "Net-(DZ20E-C)") (class "Default")
      (node (ref "DZ20") (pin "K5") (pinfunction "C_K5") (pintype "passive"))
      (node (ref "DZ21") (pin "A5") (pinfunction "A_A5") (pintype "passive"))
    )
    (net (code "106") (name "Net-(DZ21A-C)") (class "Default")
      (node (ref "DZ21") (pin "K1") (pinfunction "C_K1") (pintype "passive"))
      (node (ref "DZ22") (pin "A1") (pinfunction "A_A1") (pintype "passive"))
    )
    (net (code "107") (name "Net-(DZ21B-C)") (class "Default")
      (node (ref "DZ21") (pin "K2") (pinfunction "C_K2") (pintype "passive"))
      (node (ref "DZ22") (pin "A2") (pinfunction "A_A2") (pintype "passive"))
    )
    (net (code "108") (name "Net-(DZ21C-C)") (class "Default")
      (node (ref "DZ21") (pin "K3") (pinfunction "C_K3") (pintype "passive"))
      (node (ref "DZ22") (pin "A3") (pinfunction "A_A3") (pintype "passive"))
    )
    (net (code "109") (name "Net-(DZ21D-C)") (class "Default")
      (node (ref "DZ21") (pin "K4") (pinfunction "C_K4") (pintype "passive"))
      (node (ref "DZ22") (pin "A4") (pinfunction "A_A4") (pintype "passive"))
    )
    (net (code "110") (name "Net-(DZ21E-C)") (class "Default")
      (node (ref "DZ21") (pin "K5") (pinfunction "C_K5") (pintype "passive"))
      (node (ref "DZ22") (pin "A5") (pinfunction "A_A5") (pintype "passive"))
    )
    (net (code "111") (name "Net-(DZ22A-C)") (class "Default")
      (node (ref "DZ22") (pin "K1") (pinfunction "C_K1") (pintype "passive"))
      (node (ref "DZ23") (pin "A1") (pinfunction "A_A1") (pintype "passive"))
    )
    (net (code "112") (name "Net-(DZ22B-C)") (class "Default")
      (node (ref "DZ22") (pin "K2") (pinfunction "C_K2") (pintype "passive"))
      (node (ref "DZ23") (pin "A2") (pinfunction "A_A2") (pintype "passive"))
    )
    (net (code "113") (name "Net-(DZ22C-C)") (class "Default")
      (node (ref "DZ22") (pin "K3") (pinfunction "C_K3") (pintype "passive"))
      (node (ref "DZ23") (pin "A3") (pinfunction "A_A3") (pintype "passive"))
    )
    (net (code "114") (name "Net-(DZ22D-C)") (class "Default")
      (node (ref "DZ22") (pin "K4") (pinfunction "C_K4") (pintype "passive"))
      (node (ref "DZ23") (pin "A4") (pinfunction "A_A4") (pintype "passive"))
    )
    (net (code "115") (name "Net-(DZ22E-C)") (class "Default")
      (node (ref "D20") (pin "A") (pinfunction "A_A") (pintype "passive"))
      (node (ref "DZ22") (pin "K5") (pinfunction "C_K5") (pintype "passive"))
    )
    (net (code "116") (name "Net-(DZ23A-C)") (class "Default")
      (node (ref "DZ23") (pin "K1") (pinfunction "C_K1") (pintype "passive"))
      (node (ref "DZ24") (pin "A1") (pinfunction "A_A1") (pintype "passive"))
    )
    (net (code "117") (name "Net-(DZ23B-C)") (class "Default")
      (node (ref "DZ23") (pin "K2") (pinfunction "C_K2") (pintype "passive"))
      (node (ref "DZ24") (pin "A2") (pinfunction "A_A2") (pintype "passive"))
    )
    (net (code "118") (name "Net-(DZ23C-C)") (class "Default")
      (node (ref "DZ23") (pin "K3") (pinfunction "C_K3") (pintype "passive"))
      (node (ref "DZ24") (pin "A3") (pinfunction "A_A3") (pintype "passive"))
    )
    (net (code "119") (name "Net-(DZ23D-C)") (class "Default")
      (node (ref "DZ23") (pin "K4") (pinfunction "C_K4") (pintype "passive"))
      (node (ref "DZ24") (pin "A4") (pinfunction "A_A4") (pintype "passive"))
    )
    (net (code "120") (name "Net-(DZ24A-C)") (class "Default")
      (node (ref "DZ24") (pin "K1") (pinfunction "C_K1") (pintype "passive"))
      (node (ref "DZ25") (pin "A1") (pinfunction "A_A1") (pintype "passive"))
    )
    (net (code "121") (name "Net-(DZ24B-C)") (class "Default")
      (node (ref "DZ24") (pin "K2") (pinfunction "C_K2") (pintype "passive"))
      (node (ref "DZ25") (pin "A2") (pinfunction "A_A2") (pintype "passive"))
    )
    (net (code "122") (name "Net-(DZ24C-C)") (class "Default")
      (node (ref "DZ24") (pin "K3") (pinfunction "C_K3") (pintype "passive"))
      (node (ref "DZ25") (pin "A3") (pinfunction "A_A3") (pintype "passive"))
    )
    (net (code "123") (name "Net-(DZ24D-C)") (class "Default")
      (node (ref "DZ24") (pin "K4") (pinfunction "C_K4") (pintype "passive"))
      (node (ref "DZ25") (pin "A4") (pinfunction "A_A4") (pintype "passive"))
    )
    (net (code "124") (name "Net-(DZ24E-C)") (class "Default")
      (node (ref "DZ24") (pin "K5") (pinfunction "C_K5") (pintype "passive"))
      (node (ref "DZ25") (pin "A5") (pinfunction "A_A5") (pintype "passive"))
    )
    (net (code "125") (name "Net-(DZ26A-C)") (class "Default")
      (node (ref "DZ26") (pin "K1") (pinfunction "C_K1") (pintype "passive"))
      (node (ref "DZ27") (pin "A1") (pinfunction "A_A1") (pintype "passive"))
    )
    (net (code "126") (name "Net-(DZ26B-C)") (class "Default")
      (node (ref "DZ26") (pin "K2") (pinfunction "C_K2") (pintype "passive"))
      (node (ref "DZ27") (pin "A2") (pinfunction "A_A2") (pintype "passive"))
    )
    (net (code "127") (name "Net-(DZ27A-C)") (class "Default")
      (node (ref "DZ27") (pin "K1") (pinfunction "C_K1") (pintype "passive"))
      (node (ref "DZ28") (pin "A1") (pinfunction "A_A1") (pintype "passive"))
    )
    (net (code "128") (name "Net-(DZ27B-C)") (class "Default")
      (node (ref "DZ27") (pin "K2") (pinfunction "C_K2") (pintype "passive"))
      (node (ref "DZ28") (pin "A2") (pinfunction "A_A2") (pintype "passive"))
    )
    (net (code "129") (name "Net-(DZ28A-C)") (class "Default")
      (node (ref "DZ28") (pin "K1") (pinfunction "C_K1") (pintype "passive"))
      (node (ref "DZ29") (pin "A1") (pinfunction "A_A1") (pintype "passive"))
    )
    (net (code "130") (name "Net-(DZ28B-C)") (class "Default")
      (node (ref "DZ28") (pin "K2") (pinfunction "C_K2") (pintype "passive"))
      (node (ref "DZ29") (pin "A2") (pinfunction "A_A2") (pintype "passive"))
    )
    (net (code "131") (name "Net-(DZ29A-C)") (class "Default")
      (node (ref "DZ29") (pin "K1") (pinfunction "C_K1") (pintype "passive"))
      (node (ref "DZ30") (pin "A1") (pinfunction "A_A1") (pintype "passive"))
    )
    (net (code "132") (name "Net-(DZ29B-C)") (class "Default")
      (node (ref "DZ29") (pin "K2") (pinfunction "C_K2") (pintype "passive"))
      (node (ref "DZ30") (pin "A2") (pinfunction "A_A2") (pintype "passive"))
    )
    (net (code "133") (name "Net-(DZ30A-C)") (class "Default")
      (node (ref "DZ30") (pin "K1") (pinfunction "C_K1") (pintype "passive"))
      (node (ref "DZ31") (pin "A1") (pinfunction "A_A1") (pintype "passive"))
    )
    (net (code "134") (name "Net-(DZ30B-C)") (class "Default")
      (node (ref "DZ30") (pin "K2") (pinfunction "C_K2") (pintype "passive"))
      (node (ref "DZ31") (pin "A2") (pinfunction "A_A2") (pintype "passive"))
    )
    (net (code "135") (name "Net-(DZ31A-C)") (class "Default")
      (node (ref "DZ31") (pin "K1") (pinfunction "C_K1") (pintype "passive"))
      (node (ref "DZ32") (pin "A1") (pinfunction "A_A1") (pintype "passive"))
    )
    (net (code "136") (name "Net-(DZ31B-C)") (class "Default")
      (node (ref "DZ31") (pin "K2") (pinfunction "C_K2") (pintype "passive"))
      (node (ref "DZ32") (pin "A2") (pinfunction "A_A2") (pintype "passive"))
    )
    (net (code "137") (name "Net-(DZ32A-C)") (class "Default")
      (node (ref "DZ32") (pin "K1") (pinfunction "C_K1") (pintype "passive"))
      (node (ref "DZ33") (pin "A1") (pinfunction "A_A1") (pintype "passive"))
    )
    (net (code "138") (name "Net-(DZ32B-C)") (class "Default")
      (node (ref "DZ32") (pin "K2") (pinfunction "C_K2") (pintype "passive"))
      (node (ref "DZ33") (pin "A2") (pinfunction "A_A2") (pintype "passive"))
    )
    (net (code "139") (name "Net-(DZ33A-C)") (class "Default")
      (node (ref "DZ33") (pin "K1") (pinfunction "C_K1") (pintype "passive"))
      (node (ref "DZ34") (pin "A1") (pinfunction "A_A1") (pintype "passive"))
    )
    (net (code "140") (name "Net-(DZ33B-C)") (class "Default")
      (node (ref "DZ33") (pin "K2") (pinfunction "C_K2") (pintype "passive"))
      (node (ref "DZ34") (pin "A2") (pinfunction "A_A2") (pintype "passive"))
    )
    (net (code "141") (name "Net-(DZ34A-C)") (class "Default")
      (node (ref "DZ34") (pin "K1") (pinfunction "C_K1") (pintype "passive"))
      (node (ref "DZ35") (pin "A1") (pinfunction "A_A1") (pintype "passive"))
    )
    (net (code "142") (name "Net-(DZ34B-C)") (class "Default")
      (node (ref "DZ34") (pin "K2") (pinfunction "C_K2") (pintype "passive"))
      (node (ref "DZ35") (pin "A2") (pinfunction "A_A2") (pintype "passive"))
    )
    (net (code "143") (name "Net-(R15-Pad1)") (class "Default")
      (node (ref "R15") (pin "1") (pinfunction "1_1") (pintype "passive"))
      (node (ref "R22") (pin "2") (pinfunction "2_2") (pintype "passive"))
    )
    (net (code "144") (name "Net-(R18-Pad1)") (class "Default")
      (node (ref "R18") (pin "1") (pinfunction "1_1") (pintype "passive"))
      (node (ref "R21") (pin "2") (pinfunction "2_2") (pintype "passive"))
    )
    (net (code "145") (name "unconnected-(R1-Pad1)") (class "Default")
      (node (ref "R1") (pin "1") (pinfunction "1_1") (pintype "passive"))
    )
    (net (code "146") (name "unconnected-(R1-Pad2)") (class "Default")
      (node (ref "R1") (pin "2") (pinfunction "2_2") (pintype "passive"))
    )
    (net (code "147") (name "unconnected-(R2-Pad1)") (class "Default")
      (node (ref "R2") (pin "1") (pinfunction "1_1") (pintype "passive"))
    )
    (net (code "148") (name "unconnected-(R2-Pad2)") (class "Default")
      (node (ref "R2") (pin "2") (pinfunction "2_2") (pintype "passive"))
    )
    (net (code "149") (name "unconnected-(R3-Pad1)") (class "Default")
      (node (ref "R3") (pin "1") (pinfunction "1_1") (pintype "passive"))
    )
    (net (code "150") (name "unconnected-(R3-Pad2)") (class "Default")
      (node (ref "R3") (pin "2") (pinfunction "2_2") (pintype "passive"))
    )
    (net (code "151") (name "unconnected-(R4-Pad1)") (class "Default")
      (node (ref "R4") (pin "1") (pinfunction "1_1") (pintype "passive"))
    )
    (net (code "152") (name "unconnected-(R4-Pad2)") (class "Default")
      (node (ref "R4") (pin "2") (pinfunction "2_2") (pintype "passive"))
    )
    (net (code "153") (name "unconnected-(R5-Pad1)") (class "Default")
      (node (ref "R5") (pin "1") (pinfunction "1_1") (pintype "passive"))
    )
    (net (code "154") (name "unconnected-(R5-Pad2)") (class "Default")
      (node (ref "R5") (pin "2") (pinfunction "2_2") (pintype "passive"))
    )
    (net (code "155") (name "unconnected-(R6-Pad1)") (class "Default")
      (node (ref "R6") (pin "1") (pinfunction "1_1") (pintype "passive"))
    )
    (net (code "156") (name "unconnected-(R6-Pad2)") (class "Default")
      (node (ref "R6") (pin "2") (pinfunction "2_2") (pintype "passive"))
    )
    (net (code "157") (name "unconnected-(R7-Pad1)") (class "Default")
      (node (ref "R7") (pin "1") (pinfunction "1_1") (pintype "passive"))
    )
    (net (code "158") (name "unconnected-(R7-Pad2)") (class "Default")
      (node (ref "R7") (pin "2") (pinfunction "2_2") (pintype "passive"))
    )
    (net (code "159") (name "unconnected-(R8-Pad1)") (class "Default")
      (node (ref "R8") (pin "1") (pinfunction "1_1") (pintype "passive"))
    )
    (net (code "160") (name "unconnected-(R8-Pad2)") (class "Default")
      (node (ref "R8") (pin "2") (pinfunction "2_2") (pintype "passive"))
    )
    (net (code "161") (name "unconnected-(R9-Pad1)") (class "Default")
      (node (ref "R9") (pin "1") (pinfunction "1_1") (pintype "passive"))
    )
    (net (code "162") (name "unconnected-(R9-Pad2)") (class "Default")
      (node (ref "R9") (pin "2") (pinfunction "2_2") (pintype "passive"))
    )
    (net (code "163") (name "unconnected-(R10-Pad1)") (class "Default")
      (node (ref "R10") (pin "1") (pinfunction "1_1") (pintype "passive"))
    )
    (net (code "164") (name "unconnected-(R10-Pad2)") (class "Default")
      (node (ref "R10") (pin "2") (pinfunction "2_2") (pintype "passive"))
    )
    (net (code "165") (name "unconnected-(R11-Pad1)") (class "Default")
      (node (ref "R11") (pin "1") (pinfunction "1_1") (pintype "passive"))
    )
    (net (code "166") (name "unconnected-(R11-Pad2)") (class "Default")
      (node (ref "R11") (pin "2") (pinfunction "2_2") (pintype "passive"))
    )
    (net (code "167") (name "unconnected-(R12-Pad1)") (class "Default")
      (node (ref "R12") (pin "1") (pinfunction "1_1") (pintype "passive"))
    )
    (net (code "168") (name "unconnected-(R12-Pad2)") (class "Default")
      (node (ref "R12") (pin "2") (pinfunction "2_2") (pintype "passive"))
    )
    (net (code "169") (name "unconnected-(R13-Pad1)") (class "Default")
      (node (ref "R13") (pin "1") (pinfunction "1_1") (pintype "passive"))
    )
    (net (code "170") (name "unconnected-(R13-Pad2)") (class "Default")
      (node (ref "R13") (pin "2") (pinfunction "2_2") (pintype "passive"))
    )
    (net (code "171") (name "unconnected-(R14-Pad1)") (class "Default")
      (node (ref "R14") (pin "1") (pinfunction "1_1") (pintype "passive"))
    )
    (net (code "172") (name "unconnected-(R14-Pad2)") (class "Default")
      (node (ref "R14") (pin "2") (pinfunction "2_2") (pintype "passive"))
    )
    (net (code "173") (name "unconnected-(R15-Pad2)") (class "Default")
      (node (ref "R15") (pin "2") (pinfunction "2_2") (pintype "passive"))
    )
    (net (code "174") (name "unconnected-(R16-Pad1)") (class "Default")
      (node (ref "R16") (pin "1") (pinfunction "1_1") (pintype "passive"))
    )
    (net (code "175") (name "unconnected-(R16-Pad2)") (class "Default")
      (node (ref "R16") (pin "2") (pinfunction "2_2") (pintype "passive"))
    )
    (net (code "176") (name "unconnected-(R17-Pad1)") (class "Default")
      (node (ref "R17") (pin "1") (pinfunction "1_1") (pintype "passive"))
    )
    (net (code "177") (name "unconnected-(R17-Pad2)") (class "Default")
      (node (ref "R17") (pin "2") (pinfunction "2_2") (pintype "passive"))
    )
    (net (code "178") (name "unconnected-(R18-Pad2)") (class "Default")
      (node (ref "R18") (pin "2") (pinfunction "2_2") (pintype "passive"))
    )
    (net (code "179") (name "unconnected-(R19-Pad1)") (class "Default")
      (node (ref "R19") (pin "1") (pinfunction "1_1") (pintype "passive"))
    )
    (net (code "180") (name "unconnected-(R19-Pad2)") (class "Default")
      (node (ref "R19") (pin "2") (pinfunction "2_2") (pintype "passive"))
    )
    (net (code "181") (name "unconnected-(R20-Pad1)") (class "Default")
      (node (ref "R20") (pin "1") (pinfunction "1_1") (pintype "passive"))
    )
    (net (code "182") (name "unconnected-(R20-Pad2)") (class "Default")
      (node (ref "R20") (pin "2") (pinfunction "2_2") (pintype "passive"))
    )
    (net (code "183") (name "unconnected-(R21-Pad1)") (class "Default")
      (node (ref "R21") (pin "1") (pinfunction "1_1") (pintype "passive"))
    )
    (net (code "184") (name "unconnected-(R22-Pad1)") (class "Default")
      (node (ref "R22") (pin "1") (pinfunction "1_1") (pintype "passive"))
    )
    (net (code "185") (name "unconnected-(R25-Pad1)") (class "Default")
      (node (ref "R25") (pin "1") (pinfunction "1_1") (pintype "passive"))
    )
    (net (code "186") (name "unconnected-(R25-Pad2)") (class "Default")
      (node (ref "R25") (pin "2") (pinfunction "2_2") (pintype "passive"))
    )
    (net (code "187") (name "unconnected-(R26-Pad1)") (class "Default")
      (node (ref "R26") (pin "1") (pinfunction "1_1") (pintype "passive"))
    )
    (net (code "188") (name "unconnected-(R26-Pad2)") (class "Default")
      (node (ref "R26") (pin "2") (pinfunction "2_2") (pintype "passive"))
    )
    (net (code "189") (name "unconnected-(R27-Pad1)") (class "Default")
      (node (ref "R27") (pin "1") (pinfunction "1_1") (pintype "passive"))
    )
    (net (code "190") (name "unconnected-(R27-Pad2)") (class "Default")
      (node (ref "R27") (pin "2") (pinfunction "2_2") (pintype "passive"))
    )
    (net (code "191") (name "unconnected-(R28-Pad1)") (class "Default")
      (node (ref "R28") (pin "1") (pinfunction "1_1") (pintype "passive"))
    )
    (net (code "192") (name "unconnected-(R28-Pad2)") (class "Default")
      (node (ref "R28") (pin "2") (pinfunction "2_2") (pintype "passive"))
    )
    (net (code "193") (name "unconnected-(R29-Pad1)") (class "Default")
      (node (ref "R29") (pin "1") (pinfunction "1_1") (pintype "passive"))
    )
    (net (code "194") (name "unconnected-(R29-Pad2)") (class "Default")
      (node (ref "R29") (pin "2") (pinfunction "2_2") (pintype "passive"))
    )
    (net (code "195") (name "unconnected-(R30-Pad1)") (class "Default")
      (node (ref "R30") (pin "1") (pinfunction "1_1") (pintype "passive"))
    )
    (net (code "196") (name "unconnected-(R30-Pad2)") (class "Default")
      (node (ref "R30") (pin "2") (pinfunction "2_2") (pintype "passive"))
    )
    (net (code "197") (name "unconnected-(R31-Pad1)") (class "Default")
      (node (ref "R31") (pin "1") (pinfunction "1_1") (pintype "passive"))
    )
    (net (code "198") (name "unconnected-(R31-Pad2)") (class "Default")
      (node (ref "R31") (pin "2") (pinfunction "2_2") (pintype "passive"))
    )
    (net (code "199") (name "unconnected-(R32-Pad1)") (class "Default")
      (node (ref "R32") (pin "1") (pinfunction "1_1") (pintype "passive"))
    )
    (net (code "200") (name "unconnected-(R32-Pad2)") (class "Default")
      (node (ref "R32") (pin "2") (pinfunction "2_2") (pintype "passive"))
    )
    (net (code "201") (name "unconnected-(R33-Pad1)") (class "Default")
      (node (ref "R33") (pin "1") (pinfunction "1_1") (pintype "passive"))
    )
    (net (code "202") (name "unconnected-(R33-Pad2)") (class "Default")
      (node (ref "R33") (pin "2") (pinfunction "2_2") (pintype "passive"))
    )
    (net (code "203") (name "unconnected-(R34-Pad1)") (class "Default")
      (node (ref "R34") (pin "1") (pinfunction "1_1") (pintype "passive"))
    )
    (net (code "204") (name "unconnected-(R34-Pad2)") (class "Default")
      (node (ref "R34") (pin "2") (pinfunction "2_2") (pintype "passive"))
    )
    (net (code "205") (name "unconnected-(R35-Pad1)") (class "Default")
      (node (ref "R35") (pin "1") (pinfunction "1_1") (pintype "passive"))
    )
    (net (code "206") (name "unconnected-(R35-Pad2)") (class "Default")
      (node (ref "R35") (pin "2") (pinfunction "2_2") (pintype "passive"))
    )
    (net (code "207") (name "unconnected-(R36-Pad1)") (class "Default")
      (node (ref "R36") (pin "1") (pinfunction "1_1") (pintype "passive"))
    )
    (net (code "208") (name "unconnected-(R36-Pad2)") (class "Default")
      (node (ref "R36") (pin "2") (pinfunction "2_2") (pintype "passive"))
    )
    (net (code "209") (name "unconnected-(R37-Pad1)") (class "Default")
      (node (ref "R37") (pin "1") (pinfunction "1_1") (pintype "passive"))
    )
    (net (code "210") (name "unconnected-(R37-Pad2)") (class "Default")
      (node (ref "R37") (pin "2") (pinfunction "2_2") (pintype "passive"))
    )
    (net (code "211") (name "unconnected-(R38-Pad1)") (class "Default")
      (node (ref "R38") (pin "1") (pinfunction "1_1") (pintype "passive"))
    )
    (net (code "212") (name "unconnected-(R38-Pad2)") (class "Default")
      (node (ref "R38") (pin "2") (pinfunction "2_2") (pintype "passive"))
    )
    (net (code "213") (name "unconnected-(R39-Pad1)") (class "Default")
      (node (ref "R39") (pin "1") (pinfunction "1_1") (pintype "passive"))
    )
    (net (code "214") (name "unconnected-(R39-Pad2)") (class "Default")
      (node (ref "R39") (pin "2") (pinfunction "2_2") (pintype "passive"))
    )
    (net (code "215") (name "unconnected-(R40-Pad1)") (class "Default")
      (node (ref "R40") (pin "1") (pinfunction "1_1") (pintype "passive"))
    )
    (net (code "216") (name "unconnected-(R40-Pad2)") (class "Default")
      (node (ref "R40") (pin "2") (pinfunction "2_2") (pintype "passive"))
    )
    (net (code "217") (name "unconnected-(R41-Pad1)") (class "Default")
      (node (ref "R41") (pin "1") (pinfunction "1_1") (pintype "passive"))
    )
    (net (code "218") (name "unconnected-(R41-Pad2)") (class "Default")
      (node (ref "R41") (pin "2") (pinfunction "2_2") (pintype "passive"))
    )
    (net (code "219") (name "unconnected-(R42-Pad1)") (class "Default")
      (node (ref "R42") (pin "1") (pinfunction "1_1") (pintype "passive"))
    )
    (net (code "220") (name "unconnected-(R42-Pad2)") (class "Default")
      (node (ref "R42") (pin "2") (pinfunction "2_2") (pintype "passive"))
    )
    (net (code "221") (name "unconnected-(R43-Pad1)") (class "Default")
      (node (ref "R43") (pin "1") (pinfunction "1_1") (pintype "passive"))
    )
    (net (code "222") (name "unconnected-(R43-Pad2)") (class "Default")
      (node (ref "R43") (pin "2") (pinfunction "2_2") (pintype "passive"))
    )
    (net (code "223") (name "unconnected-(R44-Pad1)") (class "Default")
      (node (ref "R44") (pin "1") (pinfunction "1_1") (pintype "passive"))
    )
    (net (code "224") (name "unconnected-(R44-Pad2)") (class "Default")
      (node (ref "R44") (pin "2") (pinfunction "2_2") (pintype "passive"))
    )
    (net (code "225") (name "unconnected-(R45-Pad1)") (class "Default")
      (node (ref "R45") (pin "1") (pinfunction "1_1") (pintype "passive"))
    )
    (net (code "226") (name "unconnected-(R45-Pad2)") (class "Default")
      (node (ref "R45") (pin "2") (pinfunction "2_2") (pintype "passive"))
    )
    (net (code "227") (name "unconnected-(R46-Pad1)") (class "Default")
      (node (ref "R46") (pin "1") (pinfunction "1_1") (pintype "passive"))
    )
    (net (code "228") (name "unconnected-(R46-Pad2)") (class "Default")
      (node (ref "R46") (pin "2") (pinfunction "2_2") (pintype "passive"))
    )
    (net (code "229") (name "unconnected-(R47-Pad1)") (class "Default")
      (node (ref "R47") (pin "1") (pinfunction "1_1") (pintype "passive"))
    )
    (net (code "230") (name "unconnected-(R47-Pad2)") (class "Default")
      (node (ref "R47") (pin "2") (pinfunction "2_2") (pintype "passive"))
    )
    (net (code "231") (name "unconnected-(R48-Pad1)") (class "Default")
      (node (ref "R48") (pin "1") (pinfunction "1_1") (pintype "passive"))
    )
    (net (code "232") (name "unconnected-(R48-Pad2)") (class "Default")
      (node (ref "R48") (pin "2") (pinfunction "2_2") (pintype "passive"))
    )
    (net (code "233") (name "unconnected-(R49-Pad1)") (class "Default")
      (node (ref "R49") (pin "1") (pinfunction "1_1") (pintype "passive"))
    )
    (net (code "234") (name "unconnected-(R49-Pad2)") (class "Default")
      (node (ref "R49") (pin "2") (pinfunction "2_2") (pintype "passive"))
    )
    (net (code "235") (name "unconnected-(R50-Pad1)") (class "Default")
      (node (ref "R50") (pin "1") (pinfunction "1_1") (pintype "passive"))
    )
    (net (code "236") (name "unconnected-(R50-Pad2)") (class "Default")
      (node (ref "R50") (pin "2") (pinfunction "2_2") (pintype "passive"))
    )
    (net (code "237") (name "unconnected-(R51-Pad1)") (class "Default")
      (node (ref "R51") (pin "1") (pinfunction "1_1") (pintype "passive"))
    )
    (net (code "238") (name "unconnected-(R51-Pad2)") (class "Default")
      (node (ref "R51") (pin "2") (pinfunction "2_2") (pintype "passive"))
    )
    (net (code "239") (name "unconnected-(R52-Pad1)") (class "Default")
      (node (ref "R52") (pin "1") (pinfunction "1_1") (pintype "passive"))
    )
    (net (code "240") (name "unconnected-(R52-Pad2)") (class "Default")
      (node (ref "R52") (pin "2") (pinfunction "2_2") (pintype "passive"))
    )
    (net (code "241") (name "unconnected-(R53-Pad1)") (class "Default")
      (node (ref "R53") (pin "1") (pinfunction "1_1") (pintype "passive"))
    )
    (net (code "242") (name "unconnected-(R53-Pad2)") (class "Default")
      (node (ref "R53") (pin "2") (pinfunction "2_2") (pintype "passive"))
    )
    (net (code "243") (name "unconnected-(R54-Pad1)") (class "Default")
      (node (ref "R54") (pin "1") (pinfunction "1_1") (pintype "passive"))
    )
    (net (code "244") (name "unconnected-(R54-Pad2)") (class "Default")
      (node (ref "R54") (pin "2") (pinfunction "2_2") (pintype "passive"))
    )
  )
)
